# untitled.net
KiCad netlist of a schematic drawn in EAGLE
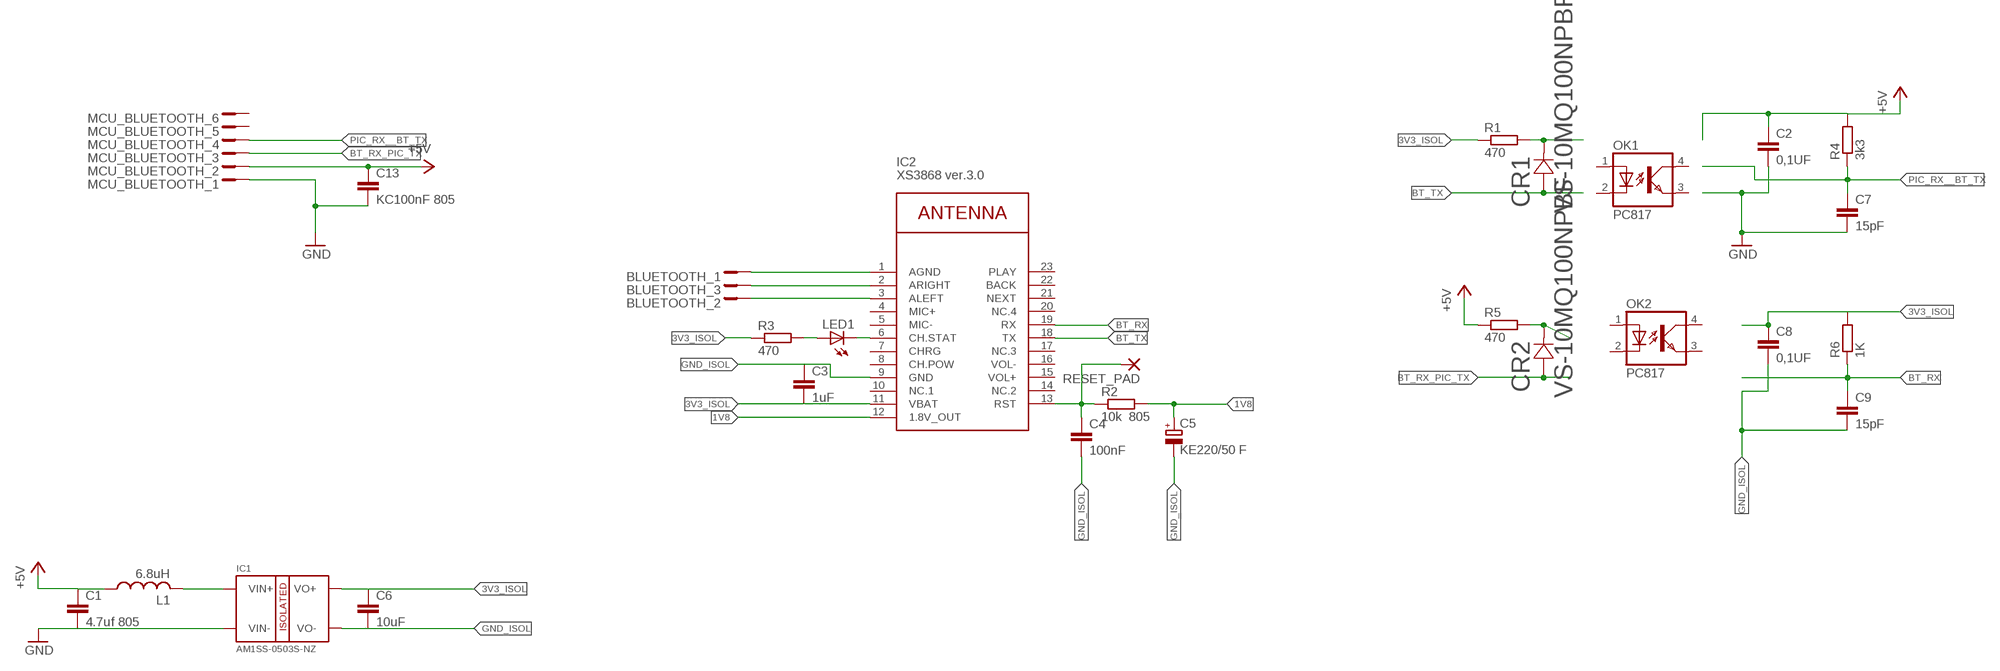
[diagram p0: schematic, sheet 1]

(export (version "E")
  (design (tool "Eeschema 10.0.6"))
  (components
    (comp (ref "BLUETOOTH")
      (value "JST_3_PIN_B3B-PH-KS")
      (footprint "eagle-import:B3B-PH-KS")
      (libsource (lib "eagle-import") (part "JST_3_PIN_B3B-PH-KS"))
    )
    (comp (ref "C1")
      (value "4.7uf 805")
      (footprint "eagle-import:C0805")
      (libsource (lib "eagle-import") (part "C-EUC0805"))
    )
    (comp (ref "C2")
      (value "0,1UF")
      (footprint "eagle-import:C0805")
      (libsource (lib "eagle-import") (part "resistor_C-EUC0805"))
    )
    (comp (ref "C3")
      (value "1uF")
      (footprint "eagle-import:C0805")
      (libsource (lib "eagle-import") (part "resistor_C-EUC0805"))
    )
    (comp (ref "C4")
      (value "100nF")
      (footprint "eagle-import:C0805")
      (libsource (lib "eagle-import") (part "resistor_C-EUC0805"))
    )
    (comp (ref "C5")
      (value "KE220/50 F")
      (footprint "eagle-import:PANASONIC_G")
      (libsource (lib "eagle-import") (part "CPOL-EUG"))
    )
    (comp (ref "C6")
      (value "10uF")
      (footprint "eagle-import:C0805")
      (libsource (lib "eagle-import") (part "resistor_C-EUC0805"))
    )
    (comp (ref "C7")
      (value "15pF")
      (footprint "eagle-import:C0805")
      (libsource (lib "eagle-import") (part "resistor_C-EUC0805"))
    )
    (comp (ref "C8")
      (value "0,1UF")
      (footprint "eagle-import:C0805")
      (libsource (lib "eagle-import") (part "resistor_C-EUC0805"))
    )
    (comp (ref "C9")
      (value "15pF")
      (footprint "eagle-import:C0805")
      (libsource (lib "eagle-import") (part "resistor_C-EUC0805"))
    )
    (comp (ref "C13")
      (value "KC100nF 805")
      (footprint "eagle-import:C0805")
      (libsource (lib "eagle-import") (part "C-EUC0805"))
    )
    (comp (ref "CR1")
      (value "VS-10MQ100NPBF")
      (footprint "eagle-import:DIODE_SMA")
      (fields (field (name "MANUFACTURER_PART_NUMBER") "VS10MQ100NPBF"))
      (libsource (lib "eagle-import") (part "VS-10MQ100NPBF"))
    )
    (comp (ref "CR2")
      (value "VS-10MQ100NPBF")
      (footprint "eagle-import:DIODE_SMA")
      (fields (field (name "MANUFACTURER_PART_NUMBER") "VS10MQ100NPBF"))
      (libsource (lib "eagle-import") (part "VS-10MQ100NPBF"))
    )
    (comp (ref "IC1")
      (value "AM1SS-0503S-NZ")
      (footprint "eagle-import:SIP4")
      (libsource (lib "eagle-import") (part "AM1SS-0503S-NZ"))
    )
    (comp (ref "IC2")
      (value "XS3868 ver.3.0")
      (footprint "eagle-import:WIRELESS-BLUETOOTH-XS3868")
      (libsource (lib "eagle-import") (part "WIRELESS-BLUETOOTH-XS3868"))
    )
    (comp (ref "L1")
      (value "6.8uH")
      (footprint "eagle-import:0204_5")
      (libsource (lib "eagle-import") (part "L-US0204/5"))
    )
    (comp (ref "LED1")
      (value "LEDSMART-LED")
      (footprint "eagle-import:SMART-LED")
      (libsource (lib "eagle-import") (part "LEDSMART-LED"))
    )
    (comp (ref "MCU_BLUETOOTH")
      (value "JST_6_PIN_B6B-PH-KS")
      (footprint "eagle-import:B6B-PH-KS")
      (libsource (lib "eagle-import") (part "JST_6_PIN_B6B-PH-KS"))
    )
    (comp (ref "OK1")
      (value "PC817")
      (footprint "eagle-import:DIL04")
      (fields (field (name "MPN") "PC817X4J000F"))
      (libsource (lib "eagle-import") (part "PC817"))
    )
    (comp (ref "OK2")
      (value "PC817")
      (footprint "eagle-import:DIL04")
      (fields (field (name "MPN") "PC817X4J000F"))
      (libsource (lib "eagle-import") (part "PC817"))
    )
    (comp (ref "R1")
      (value "470")
      (footprint "eagle-import:M0805")
      (libsource (lib "eagle-import") (part "R-EU_M0805"))
    )
    (comp (ref "R2")
      (value "10k 805")
      (footprint "eagle-import:M0805")
      (libsource (lib "eagle-import") (part "R-EU_M0805"))
    )
    (comp (ref "R3")
      (value "470")
      (footprint "eagle-import:M0805")
      (libsource (lib "eagle-import") (part "R-EU_M0805"))
    )
    (comp (ref "R4")
      (value "3k3")
      (footprint "eagle-import:M0805")
      (libsource (lib "eagle-import") (part "R-EU_M0805"))
    )
    (comp (ref "R5")
      (value "470")
      (footprint "eagle-import:M0805")
      (libsource (lib "eagle-import") (part "R-EU_M0805"))
    )
    (comp (ref "R6")
      (value "1K")
      (footprint "eagle-import:M0805")
      (libsource (lib "eagle-import") (part "R-EU_M0805"))
    )
    (comp (ref "RESET_PAD")
      (value "SMD2")
      (footprint "eagle-import:SMD1,27-2,54")
      (libsource (lib "eagle-import") (part "SMD2"))
    )
  )
  (nets
    (net (code "1") (name "+5V") (class "Default")
      (node (ref "C1") (pin "1") (pinfunction "1_1") (pintype "passive"))
      (node (ref "C13") (pin "1") (pinfunction "1_1") (pintype "passive"))
      (node (ref "C2") (pin "1") (pinfunction "1_1") (pintype "passive"))
      (node (ref "L1") (pin "1") (pinfunction "1_1") (pintype "passive"))
      (node (ref "MCU_BLUETOOTH") (pin "P$2") (pinfunction "P$1_P$2") (pintype "bidirectional"))
      (node (ref "R4") (pin "2") (pinfunction "2_2") (pintype "passive"))
      (node (ref "R5") (pin "1") (pinfunction "1_1") (pintype "passive"))
    )
    (net (code "2") (name "1V8") (class "Default")
      (node (ref "C5") (pin "+") (pinfunction "+_+") (pintype "passive"))
      (node (ref "IC2") (pin "12") (pinfunction "1.8V_OUT_12") (pintype "power_in"))
      (node (ref "R2") (pin "2") (pinfunction "2_2") (pintype "passive"))
    )
    (net (code "3") (name "3V3_ISOL") (class "Default")
      (node (ref "C3") (pin "2") (pinfunction "2_2") (pintype "passive"))
      (node (ref "C6") (pin "1") (pinfunction "1_1") (pintype "passive"))
      (node (ref "C8") (pin "1") (pinfunction "1_1") (pintype "passive"))
      (node (ref "IC1") (pin "P$3") (pinfunction "VO+_P$3") (pintype "bidirectional"))
      (node (ref "IC2") (pin "11") (pinfunction "VBAT_11") (pintype "power_in"))
      (node (ref "R1") (pin "1") (pinfunction "1_1") (pintype "passive"))
      (node (ref "R3") (pin "1") (pinfunction "1_1") (pintype "passive"))
      (node (ref "R6") (pin "2") (pinfunction "2_2") (pintype "passive"))
    )
    (net (code "4") (name "BT_RX") (class "Default")
      (node (ref "C9") (pin "1") (pinfunction "1_1") (pintype "passive"))
      (node (ref "IC2") (pin "19") (pinfunction "RX_19") (pintype "bidirectional"))
      (node (ref "R6") (pin "1") (pinfunction "1_1") (pintype "passive"))
    )
    (net (code "5") (name "BT_RX_PIC_TX") (class "Default")
      (node (ref "CR2") (pin "2") (pinfunction "22_2") (pintype "passive"))
      (node (ref "MCU_BLUETOOTH") (pin "P$3") (pinfunction "P$1_P$3") (pintype "bidirectional"))
    )
    (net (code "6") (name "BT_TX") (class "Default")
      (node (ref "CR1") (pin "2") (pinfunction "22_2") (pintype "passive"))
      (node (ref "IC2") (pin "18") (pinfunction "TX_18") (pintype "bidirectional"))
    )
    (net (code "7") (name "GND") (class "Default")
      (node (ref "C1") (pin "2") (pinfunction "2_2") (pintype "passive"))
      (node (ref "C13") (pin "2") (pinfunction "2_2") (pintype "passive"))
      (node (ref "C2") (pin "2") (pinfunction "2_2") (pintype "passive"))
      (node (ref "C7") (pin "2") (pinfunction "2_2") (pintype "passive"))
      (node (ref "IC1") (pin "P$2") (pinfunction "VIN-_P$2") (pintype "bidirectional"))
      (node (ref "MCU_BLUETOOTH") (pin "P$1") (pinfunction "P$1_P$1") (pintype "bidirectional"))
    )
    (net (code "8") (name "GND_ISOL") (class "Default")
      (node (ref "C3") (pin "1") (pinfunction "1_1") (pintype "passive"))
      (node (ref "C4") (pin "2") (pinfunction "2_2") (pintype "passive"))
      (node (ref "C5") (pin "-") (pinfunction "-_-") (pintype "passive"))
      (node (ref "C6") (pin "2") (pinfunction "2_2") (pintype "passive"))
      (node (ref "C8") (pin "2") (pinfunction "2_2") (pintype "passive"))
      (node (ref "C9") (pin "2") (pinfunction "2_2") (pintype "passive"))
      (node (ref "IC1") (pin "P$4") (pinfunction "VO-_P$4") (pintype "bidirectional"))
      (node (ref "IC2") (pin "9") (pinfunction "GND_9") (pintype "power_in"))
    )
    (net (code "9") (name "Net-(BLUETOOTHB-P$1)") (class "Default")
      (node (ref "BLUETOOTH") (pin "P$2") (pinfunction "P$1_P$2") (pintype "bidirectional"))
      (node (ref "IC2") (pin "3") (pinfunction "ALEFT_3") (pintype "output"))
    )
    (net (code "10") (name "Net-(BLUETOOTHC-P$1)") (class "Default")
      (node (ref "BLUETOOTH") (pin "P$3") (pinfunction "P$1_P$3") (pintype "bidirectional"))
      (node (ref "IC2") (pin "2") (pinfunction "ARIGHT_2") (pintype "output"))
    )
    (net (code "11") (name "Net-(CR1-11)") (class "Default")
      (node (ref "CR1") (pin "1") (pinfunction "11_1") (pintype "passive"))
      (node (ref "R1") (pin "2") (pinfunction "2_2") (pintype "passive"))
    )
    (net (code "12") (name "Net-(CR2-11)") (class "Default")
      (node (ref "CR2") (pin "1") (pinfunction "11_1") (pintype "passive"))
      (node (ref "R5") (pin "2") (pinfunction "2_2") (pintype "passive"))
    )
    (net (code "13") (name "Net-(IC1-VIN+)") (class "Default")
      (node (ref "IC1") (pin "P$1") (pinfunction "VIN+_P$1") (pintype "bidirectional"))
      (node (ref "L1") (pin "2") (pinfunction "2_2") (pintype "passive"))
    )
    (net (code "14") (name "Net-(IC2-AGND)") (class "Default")
      (node (ref "BLUETOOTH") (pin "P$1") (pinfunction "P$1_P$1") (pintype "bidirectional"))
      (node (ref "IC2") (pin "1") (pinfunction "AGND_1") (pintype "power_in"))
    )
    (net (code "15") (name "Net-(IC2-CH.STAT)") (class "Default")
      (node (ref "IC2") (pin "6") (pinfunction "CH.STAT_6") (pintype "bidirectional"))
      (node (ref "LED1") (pin "B") (pinfunction "C_B") (pintype "passive"))
    )
    (net (code "16") (name "Net-(IC2-RST)") (class "Default")
      (node (ref "C4") (pin "1") (pinfunction "1_1") (pintype "passive"))
      (node (ref "IC2") (pin "13") (pinfunction "RST_13") (pintype "power_in"))
      (node (ref "R2") (pin "1") (pinfunction "1_1") (pintype "passive"))
      (node (ref "RESET_PAD") (pin "1") (pinfunction "P_1") (pintype "passive"))
    )
    (net (code "17") (name "Net-(LED1-PadA)") (class "Default")
      (node (ref "LED1") (pin "A") (pinfunction "A_A") (pintype "passive"))
      (node (ref "R3") (pin "2") (pinfunction "2_2") (pintype "passive"))
    )
    (net (code "18") (name "PIC_RX__BT_TX") (class "Default")
      (node (ref "C7") (pin "1") (pinfunction "1_1") (pintype "passive"))
      (node (ref "MCU_BLUETOOTH") (pin "P$4") (pinfunction "P$1_P$4") (pintype "bidirectional"))
      (node (ref "R4") (pin "1") (pinfunction "1_1") (pintype "passive"))
    )
    (net (code "19") (name "unconnected-(IC2-BACK-Pad22)") (class "Default")
      (node (ref "IC2") (pin "22") (pinfunction "BACK_22") (pintype "bidirectional"))
    )
    (net (code "20") (name "unconnected-(IC2-CH.POW-Pad8)") (class "Default")
      (node (ref "IC2") (pin "8") (pinfunction "CH.POW_8") (pintype "bidirectional"))
    )
    (net (code "21") (name "unconnected-(IC2-CHRG-Pad7)") (class "Default")
      (node (ref "IC2") (pin "7") (pinfunction "CHRG_7") (pintype "bidirectional"))
    )
    (net (code "22") (name "unconnected-(IC2-MIC+-Pad4)") (class "Default")
      (node (ref "IC2") (pin "4") (pinfunction "MIC+_4") (pintype "bidirectional"))
    )
    (net (code "23") (name "unconnected-(IC2-MIC--Pad5)") (class "Default")
      (node (ref "IC2") (pin "5") (pinfunction "MIC-_5") (pintype "bidirectional"))
    )
    (net (code "24") (name "unconnected-(IC2-NC.1-Pad10)") (class "Default")
      (node (ref "IC2") (pin "10") (pinfunction "NC.1_10") (pintype "passive"))
    )
    (net (code "25") (name "unconnected-(IC2-NC.2-Pad14)") (class "Default")
      (node (ref "IC2") (pin "14") (pinfunction "NC.2_14") (pintype "passive"))
    )
    (net (code "26") (name "unconnected-(IC2-NC.3-Pad17)") (class "Default")
      (node (ref "IC2") (pin "17") (pinfunction "NC.3_17") (pintype "passive"))
    )
    (net (code "27") (name "unconnected-(IC2-NC.4-Pad20)") (class "Default")
      (node (ref "IC2") (pin "20") (pinfunction "NC.4_20") (pintype "passive"))
    )
    (net (code "28") (name "unconnected-(IC2-NEXT-Pad21)") (class "Default")
      (node (ref "IC2") (pin "21") (pinfunction "NEXT_21") (pintype "bidirectional"))
    )
    (net (code "29") (name "unconnected-(IC2-PLAY-Pad23)") (class "Default")
      (node (ref "IC2") (pin "23") (pinfunction "PLAY_23") (pintype "bidirectional"))
    )
    (net (code "30") (name "unconnected-(IC2-VOL+-Pad15)") (class "Default")
      (node (ref "IC2") (pin "15") (pinfunction "VOL+_15") (pintype "bidirectional"))
    )
    (net (code "31") (name "unconnected-(IC2-VOL--Pad16)") (class "Default")
      (node (ref "IC2") (pin "16") (pinfunction "VOL-_16") (pintype "bidirectional"))
    )
    (net (code "32") (name "unconnected-(MCU_BLUETOOTHE-P$1-PadP$5)") (class "Default")
      (node (ref "MCU_BLUETOOTH") (pin "P$5") (pinfunction "P$1_P$5") (pintype "bidirectional"))
    )
    (net (code "33") (name "unconnected-(MCU_BLUETOOTHF-P$1-PadP$6)") (class "Default")
      (node (ref "MCU_BLUETOOTH") (pin "P$6") (pinfunction "P$1_P$6") (pintype "bidirectional"))
    )
    (net (code "34") (name "unconnected-(OK1-A-Pad1)") (class "Default")
      (node (ref "OK1") (pin "1") (pinfunction "A_1") (pintype "passive"))
    )
    (net (code "35") (name "unconnected-(OK1-C-Pad2)") (class "Default")
      (node (ref "OK1") (pin "2") (pinfunction "C_2") (pintype "passive"))
    )
    (net (code "36") (name "unconnected-(OK1-COL-Pad4)") (class "Default")
      (node (ref "OK1") (pin "4") (pinfunction "COL_4") (pintype "passive"))
    )
    (net (code "37") (name "unconnected-(OK1-EMIT-Pad3)") (class "Default")
      (node (ref "OK1") (pin "3") (pinfunction "EMIT_3") (pintype "passive"))
    )
    (net (code "38") (name "unconnected-(OK2-A-Pad1)") (class "Default")
      (node (ref "OK2") (pin "1") (pinfunction "A_1") (pintype "passive"))
    )
    (net (code "39") (name "unconnected-(OK2-C-Pad2)") (class "Default")
      (node (ref "OK2") (pin "2") (pinfunction "C_2") (pintype "passive"))
    )
    (net (code "40") (name "unconnected-(OK2-COL-Pad4)") (class "Default")
      (node (ref "OK2") (pin "4") (pinfunction "COL_4") (pintype "passive"))
    )
    (net (code "41") (name "unconnected-(OK2-EMIT-Pad3)") (class "Default")
      (node (ref "OK2") (pin "3") (pinfunction "EMIT_3") (pintype "passive"))
    )
  )
)
